# Fish_and_Microchips_Schematic.net
KiCad netlist of a schematic drawn in Altium Designer
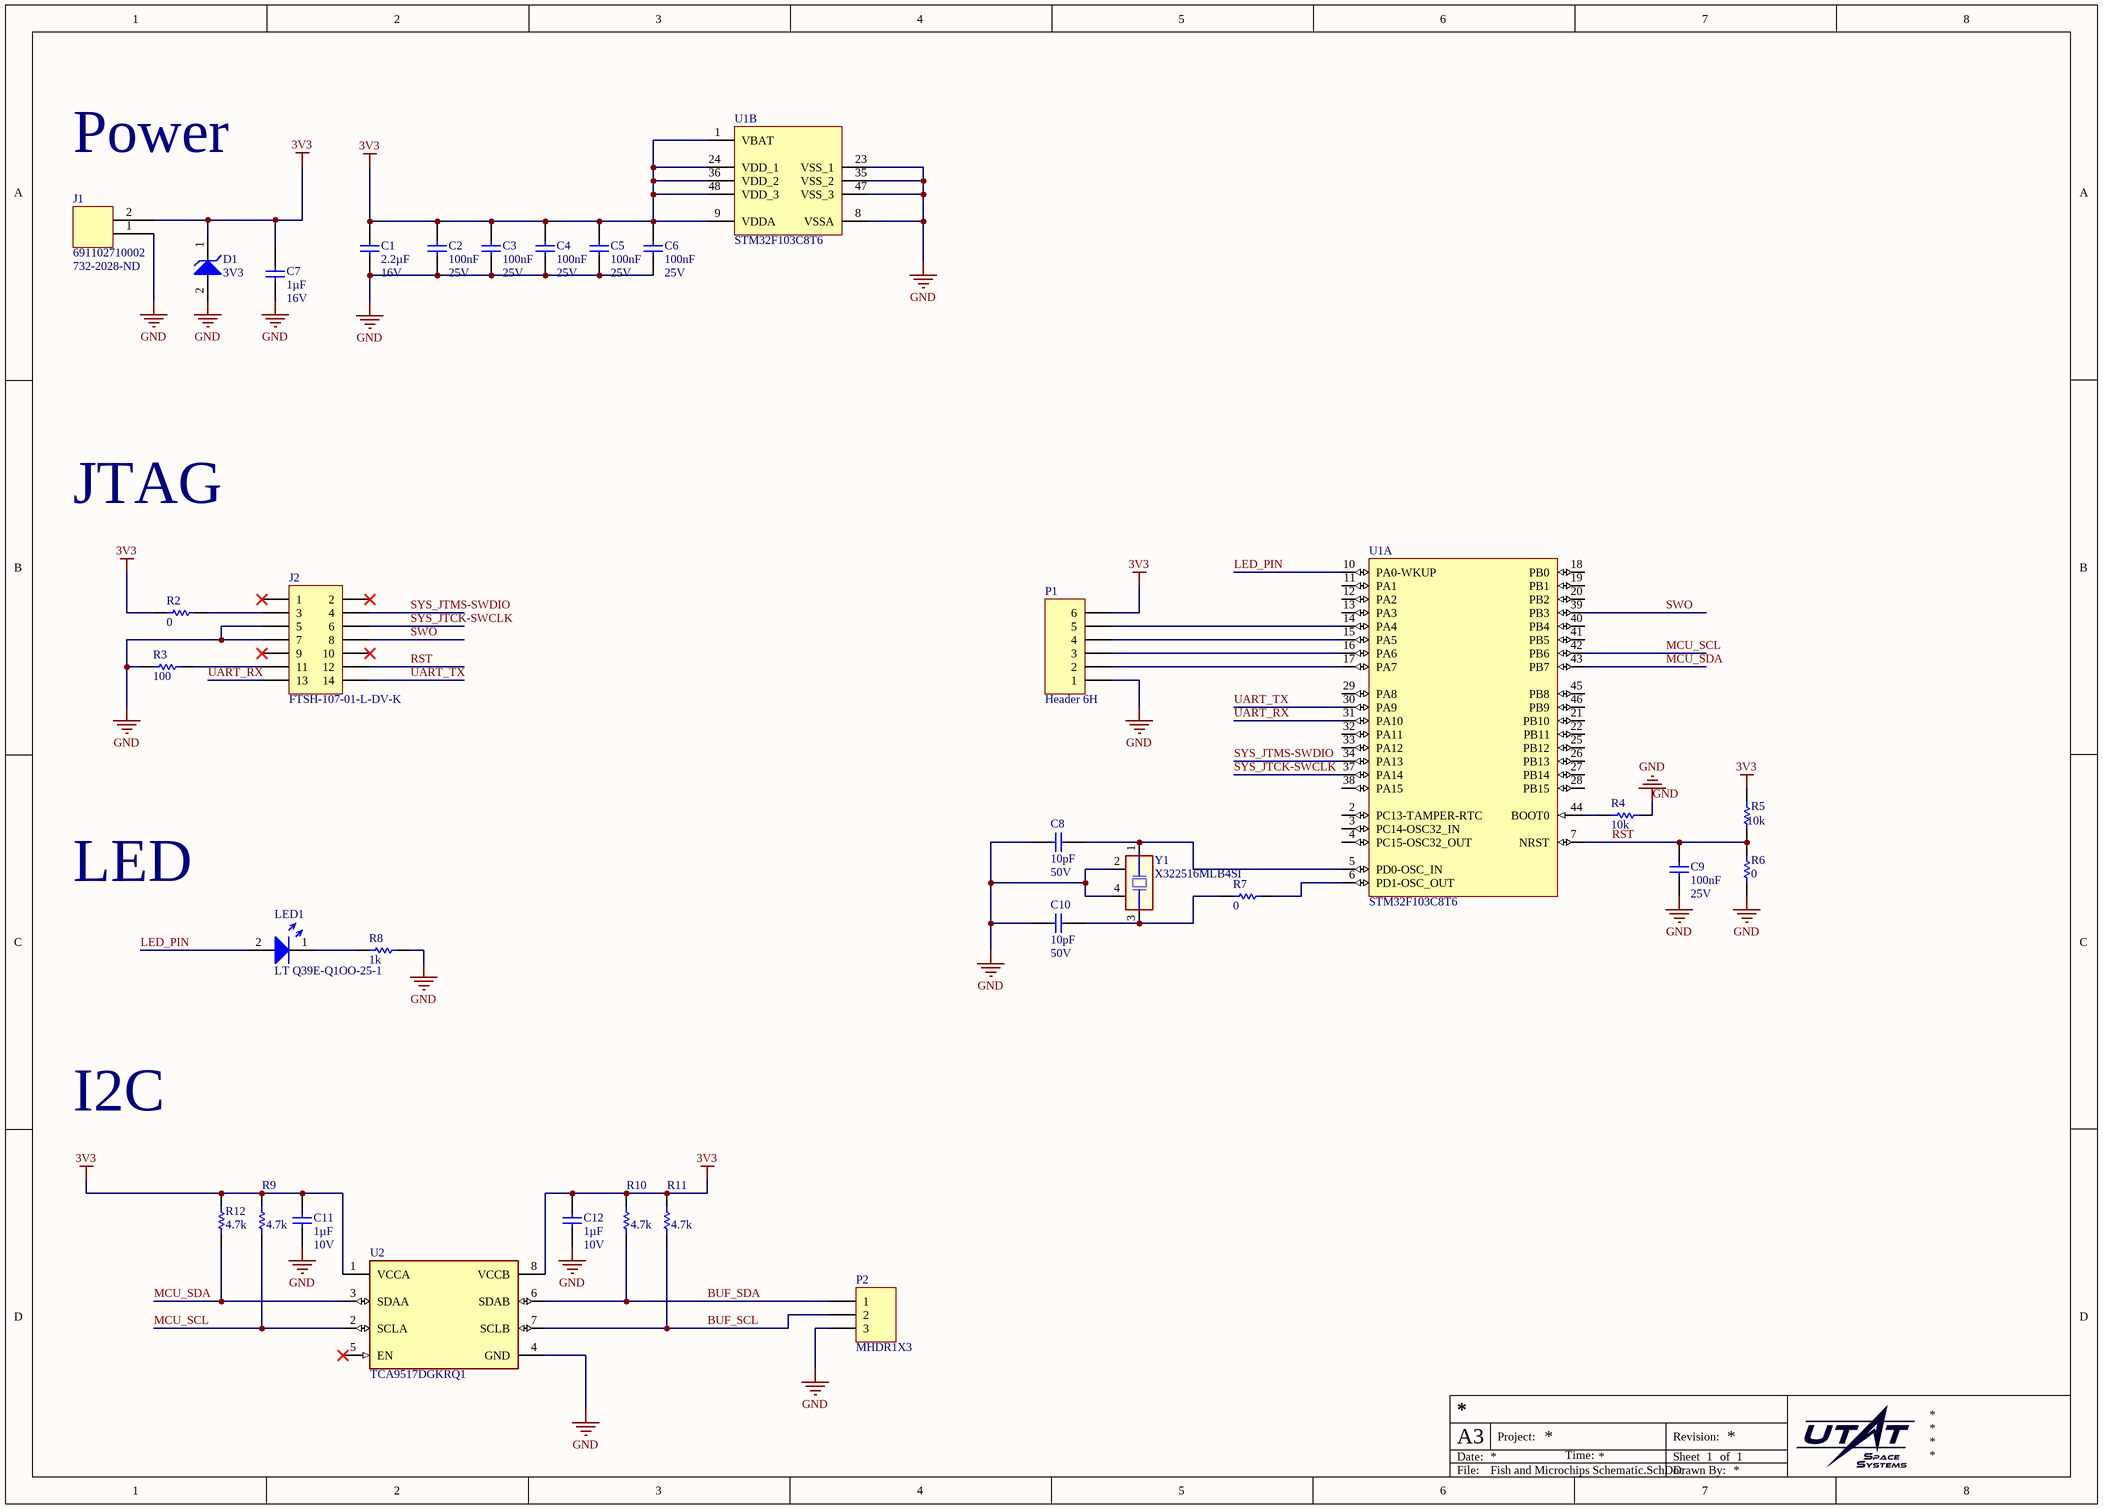
[diagram p0: Fish and Microchips Schematic.SchDoc]

(export (version "E")
  (design (tool "Eeschema 10.0.6"))
  (components
    (comp (ref "C1")
      (value "2.2µF")
      (footprint "CAP0805R")
      (description "CAP CER 2.2UF 16V X7R 0805")
      (fields
        (field (name "VOLTAGE RATING") "16V")
        (field (name "TOLERANCE") "10%")
        (field (name "MANUFACTURER") "Murata Electronics")
      )
      (libsource (lib "University of Toronto Aerospace Team") (part "Cap-2"))
    )
    (comp (ref "C2")
      (value "100nF")
      (footprint "CAP0603R")
      (description "CAP CER 0.1UF 25V X7R 0603")
      (fields
        (field (name "VOLTAGE RATING") "25V")
        (field (name "TOLERANCE") "10%")
        (field (name "MANUFACTURER") "TDK Corporation")
      )
      (libsource (lib "University of Toronto Aerospace Team") (part "Cap-2"))
    )
    (comp (ref "C3")
      (value "100nF")
      (footprint "CAP0603R")
      (description "CAP CER 0.1UF 25V X7R 0603")
      (fields
        (field (name "VOLTAGE RATING") "25V")
        (field (name "TOLERANCE") "10%")
        (field (name "MANUFACTURER") "TDK Corporation")
      )
      (libsource (lib "University of Toronto Aerospace Team") (part "Cap-2"))
    )
    (comp (ref "C4")
      (value "100nF")
      (footprint "CAP0603R")
      (description "CAP CER 0.1UF 25V X7R 0603")
      (fields
        (field (name "VOLTAGE RATING") "25V")
        (field (name "TOLERANCE") "10%")
        (field (name "MANUFACTURER") "TDK Corporation")
      )
      (libsource (lib "University of Toronto Aerospace Team") (part "Cap-2"))
    )
    (comp (ref "C5")
      (value "100nF")
      (footprint "CAP0603R")
      (description "CAP CER 0.1UF 25V X7R 0603")
      (fields
        (field (name "VOLTAGE RATING") "25V")
        (field (name "TOLERANCE") "10%")
        (field (name "MANUFACTURER") "TDK Corporation")
      )
      (libsource (lib "University of Toronto Aerospace Team") (part "Cap-2"))
    )
    (comp (ref "C6")
      (value "100nF")
      (footprint "CAP0603R")
      (description "CAP CER 0.1UF 25V X7R 0603")
      (fields
        (field (name "VOLTAGE RATING") "25V")
        (field (name "TOLERANCE") "10%")
        (field (name "MANUFACTURER") "TDK Corporation")
      )
      (libsource (lib "University of Toronto Aerospace Team") (part "Cap-2"))
    )
    (comp (ref "C7")
      (value "1µF")
      (footprint "CAP0805R")
      (description "CAP CER 1UF 16V X7R 0805")
      (fields
        (field (name "VOLTAGE RATING") "16V")
        (field (name "MANUFACTURER") "Murata Electronics")
        (field (name "TOLERANCE") "10%")
      )
      (libsource (lib "University of Toronto Aerospace Team") (part "Cap-2"))
    )
    (comp (ref "C8")
      (value "10pF")
      (footprint "CAP0402R")
      (description "CAP CER 10PF 50V C0G/NP0 0402")
      (fields
        (field (name "VOLTAGE RATING") "50V")
        (field (name "TOLERANCE") "5%")
        (field (name "MANUFACTURER") "Murata Electronics")
      )
      (libsource (lib "University of Toronto Aerospace Team") (part "Cap-2"))
    )
    (comp (ref "C9")
      (value "100nF")
      (footprint "CAP0603R")
      (description "CAP CER 0.1UF 25V X7R 0603")
      (fields
        (field (name "VOLTAGE RATING") "25V")
        (field (name "TOLERANCE") "10%")
        (field (name "MANUFACTURER") "TDK Corporation")
      )
      (libsource (lib "University of Toronto Aerospace Team") (part "Cap-2"))
    )
    (comp (ref "C10")
      (value "10pF")
      (footprint "CAP0402R")
      (description "CAP CER 10PF 50V C0G/NP0 0402")
      (fields
        (field (name "VOLTAGE RATING") "50V")
        (field (name "TOLERANCE") "5%")
        (field (name "MANUFACTURER") "Murata Electronics")
      )
      (libsource (lib "University of Toronto Aerospace Team") (part "Cap-2"))
    )
    (comp (ref "C11")
      (value "1µF")
      (footprint "CAP0805R")
      (description "CAP CER 1UF 10V X7R 0805")
      (fields
        (field (name "VOLTAGE RATING") "10V")
        (field (name "MANUFACTURER") "Taiyo Yuden")
        (field (name "TOLERANCE") "10%")
      )
      (libsource (lib "University of Toronto Aerospace Team") (part "Cap-2"))
    )
    (comp (ref "C12")
      (value "1µF")
      (footprint "CAP0805R")
      (description "CAP CER 1UF 10V X7R 0805")
      (fields
        (field (name "VOLTAGE RATING") "10V")
        (field (name "MANUFACTURER") "Taiyo Yuden")
        (field (name "TOLERANCE") "10%")
      )
      (libsource (lib "University of Toronto Aerospace Team") (part "Cap-2"))
    )
    (comp (ref "D1")
      (value "3V3")
      (footprint "ONSC-SOD-323-2-477-02_V")
      (description "Zener Diode, 3.3V V(Z), 6%, 0.3W, Silicon, Unidirectional")
      (libsource (lib "University of Toronto Aerospace Team") (part "ONSC-K1A2-2"))
    )
    (comp (ref "J1")
      (value "691102710002")
      (footprint "CON2_SCREW_5.00MM_691102710002")
      (description "2 Position Wire to Board Terminal Block Horizontal with Board 0.197\" (5.00mm) Through Hole")
      (fields
        (field (name "SUPPLIER PART NUMBER 1") "732-2028-ND")
        (field (name "MANUFACTURER") "Würth Elektronik")
      )
      (libsource (lib "University of Toronto Aerospace Team") (part "691102710002"))
    )
    (comp (ref "J2")
      (value "FTSH-107-01-L-DV-K")
      (footprint "FP-FTSH-107-01-L-DV-K-MFG")
      (description "Conn Unshrouded Header HDR 14 POS 1.27mm Solder ST Top Entry SMD TIGER CLAW™ Tube")
      (libsource (lib "University of Toronto Aerospace Team") (part "Header 7X2H"))
    )
    (comp (ref "LED1")
      (value "LT Q39E-Q1OO-25-1")
      (footprint "LED0603")
      (description "LED GREEN DIFFUSED 0603 SMD")
      (fields (field (name "MANUFACTURER") "OSRAM Opto Semiconductors Inc."))
      (libsource (lib "University of Toronto Aerospace Team") (part "LED-2"))
    )
    (comp (ref "P1")
      (value "Header 6H")
      (footprint "HDR1X6H")
      (description "Header, 6-Pin, Right Angle")
      (fields (field (name "PUBLISHER") "Altium Limited"))
      (libsource (lib "University of Toronto Aerospace Team") (part "Header 6H"))
    )
    (comp (ref "P2")
      (value "MHDR1X3")
      (footprint "MHDR1X3")
      (description "Header, 3-Pin")
      (fields (field (name "PUBLISHER") "Altium Limited"))
      (libsource (lib "University of Toronto Aerospace Team") (part "Header 3H"))
    )
    (comp (ref "R2")
      (value "0")
      (footprint "RES0805R")
      (description "RES SMD 0 OHM JUMPER 1/8W 0805")
      (fields (field (name "MANUFACTURER") "Panasonic") (field (name "POWER") "125mW"))
      (libsource (lib "University of Toronto Aerospace Team") (part "Res-2"))
    )
    (comp (ref "R3")
      (value "100")
      (footprint "RES0603R")
      (description "RES SMD 100 OHM 5% 1/10W 0603")
      (fields (field (name "POWER") "100mW") (field (name "TOLERANCE") "5%"))
      (libsource (lib "University of Toronto Aerospace Team") (part "Res-2"))
    )
    (comp (ref "R4")
      (value "10k")
      (footprint "RES0603R")
      (description "RES SMD 10K OHM 5% 1/10W 0603")
      (fields (field (name "POWER") "100mW") (field (name "TOLERANCE") "5%"))
      (libsource (lib "University of Toronto Aerospace Team") (part "Res-2"))
    )
    (comp (ref "R5")
      (value "10k")
      (footprint "RES0603R")
      (description "RES SMD 10K OHM 5% 1/10W 0603")
      (fields (field (name "POWER") "100mW") (field (name "TOLERANCE") "5%"))
      (libsource (lib "University of Toronto Aerospace Team") (part "Res-2"))
    )
    (comp (ref "R6")
      (value "0")
      (footprint "RES0805R")
      (description "RES SMD 0 OHM JUMPER 1/8W 0805")
      (fields (field (name "MANUFACTURER") "Panasonic") (field (name "POWER") "125mW"))
      (libsource (lib "University of Toronto Aerospace Team") (part "Res-2"))
    )
    (comp (ref "R7")
      (value "0")
      (footprint "RES0805R")
      (description "RES SMD 0 OHM JUMPER 1/8W 0805")
      (fields (field (name "MANUFACTURER") "Panasonic") (field (name "POWER") "125mW"))
      (libsource (lib "University of Toronto Aerospace Team") (part "Res-2"))
    )
    (comp (ref "R8")
      (value "1k")
      (footprint "RES0805R")
      (description "RES SMD 1K OHM 1% 1/8W 0805")
      (fields (field (name "MANUFACTURER") "Vishay Dale") (field (name "POWER") "125mW"))
      (libsource (lib "University of Toronto Aerospace Team") (part "Res-2"))
    )
    (comp (ref "R9")
      (value "4.7k")
      (footprint "RES0402R")
      (description "RES SMD 4.7K OHM 5% 1/10W 0402")
      (fields (field (name "TOLERANCE") "5%") (field (name "POWER") "100mW"))
      (libsource (lib "University of Toronto Aerospace Team") (part "Res-2"))
    )
    (comp (ref "R10")
      (value "4.7k")
      (footprint "RES0402R")
      (description "RES SMD 4.7K OHM 5% 1/10W 0402")
      (fields (field (name "TOLERANCE") "5%") (field (name "POWER") "100mW"))
      (libsource (lib "University of Toronto Aerospace Team") (part "Res-2"))
    )
    (comp (ref "R11")
      (value "4.7k")
      (footprint "RES0402R")
      (description "RES SMD 4.7K OHM 5% 1/10W 0402")
      (fields (field (name "TOLERANCE") "5%") (field (name "POWER") "100mW"))
      (libsource (lib "University of Toronto Aerospace Team") (part "Res-2"))
    )
    (comp (ref "R12")
      (value "4.7k")
      (footprint "RES0402R")
      (description "RES SMD 4.7K OHM 5% 1/10W 0402")
      (fields (field (name "TOLERANCE") "5%") (field (name "POWER") "100mW"))
      (libsource (lib "University of Toronto Aerospace Team") (part "Res-2"))
    )
    (comp (ref "U1")
      (value "STM32F103C8T6")
      (footprint "STM-LQFP48_M")
      (description "RISC Microcontroller, 32-Bit, FLASH, STM32 CPU, 72MHz, CMOS, PQFP48")
      (libsource (lib "University of Toronto Aerospace Team") (part "MC-ARM-STM32F103X8_B-SQ48"))
    )
    (comp (ref "U2")
      (value "TCA9517DGKRQ1")
      (footprint "FP-DGK0008A-MFG")
      (description "Voltage Level Translator Bidirectional 1 Circuit 2 Channel 8-VSSOP")
      (libsource (lib "University of Toronto Aerospace Team") (part "TCA9517DGKRQ1"))
    )
    (comp (ref "Y1")
      (value "X322516MLB4SI")
      (footprint "X322516MLB4SI-Footprint-1")
      (description "16MHz Surface Mount Crystal 9pF ±10ppm ±20ppm SMD3225-4P Crystals ROHS")
      (libsource (lib "University of Toronto Aerospace Team") (part "CRYSTAL-2"))
    )
  )
  (nets
    (net (code "1") (name "/BUF_SCL") (class "Default")
      (node (ref "P2") (pin "2") (pinfunction "2_2") (pintype "passive"))
      (node (ref "R11") (pin "1") (pinfunction "1_1") (pintype "passive"))
      (node (ref "U2") (pin "7") (pinfunction "SCLB_7") (pintype "bidirectional"))
    )
    (net (code "2") (name "/BUF_SDA") (class "Default")
      (node (ref "P2") (pin "1") (pinfunction "1_1") (pintype "passive"))
      (node (ref "R10") (pin "1") (pinfunction "1_1") (pintype "passive"))
      (node (ref "U2") (pin "6") (pinfunction "SDAB_6") (pintype "bidirectional"))
    )
    (net (code "3") (name "/LED_PIN") (class "Default")
      (node (ref "LED1") (pin "2") (pinfunction "Anode_2") (pintype "passive"))
      (node (ref "U1") (pin "10") (pinfunction "PA0-WKUP_10") (pintype "bidirectional"))
    )
    (net (code "4") (name "/MCU_SCL") (class "Default")
      (node (ref "R9") (pin "1") (pinfunction "1_1") (pintype "passive"))
      (node (ref "U1") (pin "42") (pinfunction "PB6_42") (pintype "bidirectional"))
      (node (ref "U2") (pin "2") (pinfunction "SCLA_2") (pintype "bidirectional"))
    )
    (net (code "5") (name "/MCU_SDA") (class "Default")
      (node (ref "R12") (pin "1") (pinfunction "1_1") (pintype "passive"))
      (node (ref "U1") (pin "43") (pinfunction "PB7_43") (pintype "bidirectional"))
      (node (ref "U2") (pin "3") (pinfunction "SDAA_3") (pintype "bidirectional"))
    )
    (net (code "6") (name "/RST") (class "Default")
      (node (ref "C9") (pin "2") (pinfunction "2_2") (pintype "passive"))
      (node (ref "J2") (pin "12") (pinfunction "12_12") (pintype "passive"))
      (node (ref "R5") (pin "1") (pinfunction "1_1") (pintype "passive"))
      (node (ref "R6") (pin "2") (pinfunction "2_2") (pintype "passive"))
      (node (ref "U1") (pin "7") (pinfunction "NRST_7") (pintype "bidirectional"))
    )
    (net (code "7") (name "/SWO") (class "Default")
      (node (ref "J2") (pin "8") (pinfunction "8_8") (pintype "passive"))
      (node (ref "U1") (pin "39") (pinfunction "PB3_39") (pintype "bidirectional"))
    )
    (net (code "8") (name "/SYS_JTCK-SWCLK") (class "Default")
      (node (ref "J2") (pin "6") (pinfunction "6_6") (pintype "passive"))
      (node (ref "U1") (pin "37") (pinfunction "PA14_37") (pintype "bidirectional"))
    )
    (net (code "9") (name "/SYS_JTMS-SWDIO") (class "Default")
      (node (ref "J2") (pin "4") (pinfunction "4_4") (pintype "passive"))
      (node (ref "U1") (pin "34") (pinfunction "PA13_34") (pintype "bidirectional"))
    )
    (net (code "10") (name "/UART_RX") (class "Default")
      (node (ref "J2") (pin "13") (pinfunction "13_13") (pintype "passive"))
      (node (ref "U1") (pin "31") (pinfunction "PA10_31") (pintype "bidirectional"))
    )
    (net (code "11") (name "/UART_TX") (class "Default")
      (node (ref "J2") (pin "14") (pinfunction "14_14") (pintype "passive"))
      (node (ref "U1") (pin "30") (pinfunction "PA9_30") (pintype "bidirectional"))
    )
    (net (code "12") (name "3V3") (class "Default")
      (node (ref "C1") (pin "2") (pinfunction "2_2") (pintype "passive"))
      (node (ref "C11") (pin "2") (pinfunction "2_2") (pintype "passive"))
      (node (ref "C12") (pin "2") (pinfunction "2_2") (pintype "passive"))
      (node (ref "C2") (pin "2") (pinfunction "2_2") (pintype "passive"))
      (node (ref "C3") (pin "2") (pinfunction "2_2") (pintype "passive"))
      (node (ref "C4") (pin "2") (pinfunction "2_2") (pintype "passive"))
      (node (ref "C5") (pin "2") (pinfunction "2_2") (pintype "passive"))
      (node (ref "C6") (pin "2") (pinfunction "2_2") (pintype "passive"))
      (node (ref "C7") (pin "2") (pinfunction "2_2") (pintype "passive"))
      (node (ref "D1") (pin "1") (pinfunction "K_1") (pintype "passive"))
      (node (ref "J1") (pin "2") (pinfunction "2_2") (pintype "passive"))
      (node (ref "P1") (pin "6") (pinfunction "6_6") (pintype "passive"))
      (node (ref "R10") (pin "2") (pinfunction "2_2") (pintype "passive"))
      (node (ref "R11") (pin "2") (pinfunction "2_2") (pintype "passive"))
      (node (ref "R12") (pin "2") (pinfunction "2_2") (pintype "passive"))
      (node (ref "R2") (pin "1") (pinfunction "1_1") (pintype "passive"))
      (node (ref "R5") (pin "2") (pinfunction "2_2") (pintype "passive"))
      (node (ref "R9") (pin "2") (pinfunction "2_2") (pintype "passive"))
      (node (ref "U1") (pin "1") (pinfunction "VBAT_1") (pintype "power_in"))
      (node (ref "U1") (pin "24") (pinfunction "VDD_1_24") (pintype "power_in"))
      (node (ref "U1") (pin "36") (pinfunction "VDD_2_36") (pintype "power_in"))
      (node (ref "U1") (pin "48") (pinfunction "VDD_3_48") (pintype "power_in"))
      (node (ref "U1") (pin "9") (pinfunction "VDDA_9") (pintype "power_in"))
      (node (ref "U2") (pin "1") (pinfunction "VCCA_1") (pintype "power_in"))
      (node (ref "U2") (pin "8") (pinfunction "VCCB_8") (pintype "power_in"))
    )
    (net (code "13") (name "GND") (class "Default")
      (node (ref "C1") (pin "1") (pinfunction "1_1") (pintype "passive"))
      (node (ref "C10") (pin "1") (pinfunction "1_1") (pintype "passive"))
      (node (ref "C11") (pin "1") (pinfunction "1_1") (pintype "passive"))
      (node (ref "C12") (pin "1") (pinfunction "1_1") (pintype "passive"))
      (node (ref "C2") (pin "1") (pinfunction "1_1") (pintype "passive"))
      (node (ref "C3") (pin "1") (pinfunction "1_1") (pintype "passive"))
      (node (ref "C4") (pin "1") (pinfunction "1_1") (pintype "passive"))
      (node (ref "C5") (pin "1") (pinfunction "1_1") (pintype "passive"))
      (node (ref "C6") (pin "1") (pinfunction "1_1") (pintype "passive"))
      (node (ref "C7") (pin "1") (pinfunction "1_1") (pintype "passive"))
      (node (ref "C8") (pin "2") (pinfunction "2_2") (pintype "passive"))
      (node (ref "C9") (pin "1") (pinfunction "1_1") (pintype "passive"))
      (node (ref "D1") (pin "2") (pinfunction "A_2") (pintype "passive"))
      (node (ref "J1") (pin "1") (pinfunction "1_1") (pintype "passive"))
      (node (ref "J2") (pin "5") (pinfunction "5_5") (pintype "passive"))
      (node (ref "J2") (pin "7") (pinfunction "7_7") (pintype "passive"))
      (node (ref "P1") (pin "1") (pinfunction "1_1") (pintype "passive"))
      (node (ref "P2") (pin "3") (pinfunction "3_3") (pintype "passive"))
      (node (ref "R3") (pin "1") (pinfunction "1_1") (pintype "passive"))
      (node (ref "R4") (pin "2") (pinfunction "2_2") (pintype "passive"))
      (node (ref "R6") (pin "1") (pinfunction "1_1") (pintype "passive"))
      (node (ref "R8") (pin "2") (pinfunction "2_2") (pintype "passive"))
      (node (ref "U1") (pin "23") (pinfunction "VSS_1_23") (pintype "power_in"))
      (node (ref "U1") (pin "35") (pinfunction "VSS_2_35") (pintype "power_in"))
      (node (ref "U1") (pin "47") (pinfunction "VSS_3_47") (pintype "power_in"))
      (node (ref "U1") (pin "8") (pinfunction "VSSA_8") (pintype "power_in"))
      (node (ref "U2") (pin "4") (pinfunction "GND_4") (pintype "power_in"))
      (node (ref "Y1") (pin "2") (pinfunction "GND_2") (pintype "passive"))
      (node (ref "Y1") (pin "4") (pinfunction "GND_4") (pintype "passive"))
    )
    (net (code "14") (name "Net-(J2-Pad3)") (class "Default")
      (node (ref "J2") (pin "3") (pinfunction "3_3") (pintype "passive"))
      (node (ref "R2") (pin "2") (pinfunction "2_2") (pintype "passive"))
    )
    (net (code "15") (name "Net-(J2-Pad11)") (class "Default")
      (node (ref "J2") (pin "11") (pinfunction "11_11") (pintype "passive"))
      (node (ref "R3") (pin "2") (pinfunction "2_2") (pintype "passive"))
    )
    (net (code "16") (name "Net-(LED1-Cathode)") (class "Default")
      (node (ref "LED1") (pin "1") (pinfunction "Cathode_1") (pintype "passive"))
      (node (ref "R8") (pin "1") (pinfunction "1_1") (pintype "passive"))
    )
    (net (code "17") (name "Net-(U1A-BOOT0)") (class "Default")
      (node (ref "R4") (pin "1") (pinfunction "1_1") (pintype "passive"))
      (node (ref "U1") (pin "44") (pinfunction "BOOT0_44") (pintype "input"))
    )
    (net (code "18") (name "Net-(U1A-PA4)") (class "Default")
      (node (ref "P1") (pin "5") (pinfunction "5_5") (pintype "passive"))
      (node (ref "U1") (pin "14") (pinfunction "PA4_14") (pintype "bidirectional"))
    )
    (net (code "19") (name "Net-(U1A-PA5)") (class "Default")
      (node (ref "P1") (pin "4") (pinfunction "4_4") (pintype "passive"))
      (node (ref "U1") (pin "15") (pinfunction "PA5_15") (pintype "bidirectional"))
    )
    (net (code "20") (name "Net-(U1A-PA6)") (class "Default")
      (node (ref "P1") (pin "3") (pinfunction "3_3") (pintype "passive"))
      (node (ref "U1") (pin "16") (pinfunction "PA6_16") (pintype "bidirectional"))
    )
    (net (code "21") (name "Net-(U1A-PA7)") (class "Default")
      (node (ref "P1") (pin "2") (pinfunction "2_2") (pintype "passive"))
      (node (ref "U1") (pin "17") (pinfunction "PA7_17") (pintype "bidirectional"))
    )
    (net (code "22") (name "Net-(U1A-PD0-OSC_IN)") (class "Default")
      (node (ref "C8") (pin "1") (pinfunction "1_1") (pintype "passive"))
      (node (ref "U1") (pin "5") (pinfunction "PD0-OSC_IN_5") (pintype "bidirectional"))
      (node (ref "Y1") (pin "1") (pinfunction "OSC1_1") (pintype "passive"))
    )
    (net (code "23") (name "Net-(U1A-PD1-OSC_OUT)") (class "Default")
      (node (ref "R7") (pin "2") (pinfunction "2_2") (pintype "passive"))
      (node (ref "U1") (pin "6") (pinfunction "PD1-OSC_OUT_6") (pintype "bidirectional"))
    )
    (net (code "24") (name "Net-(Y1-OSC2)") (class "Default")
      (node (ref "C10") (pin "2") (pinfunction "2_2") (pintype "passive"))
      (node (ref "R7") (pin "1") (pinfunction "1_1") (pintype "passive"))
      (node (ref "Y1") (pin "3") (pinfunction "OSC2_3") (pintype "passive"))
    )
    (net (code "25") (name "unconnected-(J2-Pad1)") (class "Default")
      (node (ref "J2") (pin "1") (pinfunction "1_1") (pintype "passive+no_connect"))
    )
    (net (code "26") (name "unconnected-(J2-Pad2)") (class "Default")
      (node (ref "J2") (pin "2") (pinfunction "2_2") (pintype "passive+no_connect"))
    )
    (net (code "27") (name "unconnected-(J2-Pad9)") (class "Default")
      (node (ref "J2") (pin "9") (pinfunction "9_9") (pintype "passive+no_connect"))
    )
    (net (code "28") (name "unconnected-(J2-Pad10)") (class "Default")
      (node (ref "J2") (pin "10") (pinfunction "10_10") (pintype "passive+no_connect"))
    )
    (net (code "29") (name "unconnected-(U1A-PA1-Pad11)") (class "Default")
      (node (ref "U1") (pin "11") (pinfunction "PA1_11") (pintype "bidirectional"))
    )
    (net (code "30") (name "unconnected-(U1A-PA2-Pad12)") (class "Default")
      (node (ref "U1") (pin "12") (pinfunction "PA2_12") (pintype "bidirectional"))
    )
    (net (code "31") (name "unconnected-(U1A-PA3-Pad13)") (class "Default")
      (node (ref "U1") (pin "13") (pinfunction "PA3_13") (pintype "bidirectional"))
    )
    (net (code "32") (name "unconnected-(U1A-PA8-Pad29)") (class "Default")
      (node (ref "U1") (pin "29") (pinfunction "PA8_29") (pintype "bidirectional"))
    )
    (net (code "33") (name "unconnected-(U1A-PA11-Pad32)") (class "Default")
      (node (ref "U1") (pin "32") (pinfunction "PA11_32") (pintype "bidirectional"))
    )
    (net (code "34") (name "unconnected-(U1A-PA12-Pad33)") (class "Default")
      (node (ref "U1") (pin "33") (pinfunction "PA12_33") (pintype "bidirectional"))
    )
    (net (code "35") (name "unconnected-(U1A-PA15-Pad38)") (class "Default")
      (node (ref "U1") (pin "38") (pinfunction "PA15_38") (pintype "bidirectional"))
    )
    (net (code "36") (name "unconnected-(U1A-PB0-Pad18)") (class "Default")
      (node (ref "U1") (pin "18") (pinfunction "PB0_18") (pintype "bidirectional"))
    )
    (net (code "37") (name "unconnected-(U1A-PB1-Pad19)") (class "Default")
      (node (ref "U1") (pin "19") (pinfunction "PB1_19") (pintype "bidirectional"))
    )
    (net (code "38") (name "unconnected-(U1A-PB2-Pad20)") (class "Default")
      (node (ref "U1") (pin "20") (pinfunction "PB2_20") (pintype "bidirectional"))
    )
    (net (code "39") (name "unconnected-(U1A-PB4-Pad40)") (class "Default")
      (node (ref "U1") (pin "40") (pinfunction "PB4_40") (pintype "bidirectional"))
    )
    (net (code "40") (name "unconnected-(U1A-PB5-Pad41)") (class "Default")
      (node (ref "U1") (pin "41") (pinfunction "PB5_41") (pintype "bidirectional"))
    )
    (net (code "41") (name "unconnected-(U1A-PB8-Pad45)") (class "Default")
      (node (ref "U1") (pin "45") (pinfunction "PB8_45") (pintype "bidirectional"))
    )
    (net (code "42") (name "unconnected-(U1A-PB9-Pad46)") (class "Default")
      (node (ref "U1") (pin "46") (pinfunction "PB9_46") (pintype "bidirectional"))
    )
    (net (code "43") (name "unconnected-(U1A-PB10-Pad21)") (class "Default")
      (node (ref "U1") (pin "21") (pinfunction "PB10_21") (pintype "bidirectional"))
    )
    (net (code "44") (name "unconnected-(U1A-PB11-Pad22)") (class "Default")
      (node (ref "U1") (pin "22") (pinfunction "PB11_22") (pintype "bidirectional"))
    )
    (net (code "45") (name "unconnected-(U1A-PB12-Pad25)") (class "Default")
      (node (ref "U1") (pin "25") (pinfunction "PB12_25") (pintype "bidirectional"))
    )
    (net (code "46") (name "unconnected-(U1A-PB13-Pad26)") (class "Default")
      (node (ref "U1") (pin "26") (pinfunction "PB13_26") (pintype "bidirectional"))
    )
    (net (code "47") (name "unconnected-(U1A-PB14-Pad27)") (class "Default")
      (node (ref "U1") (pin "27") (pinfunction "PB14_27") (pintype "bidirectional"))
    )
    (net (code "48") (name "unconnected-(U1A-PB15-Pad28)") (class "Default")
      (node (ref "U1") (pin "28") (pinfunction "PB15_28") (pintype "bidirectional"))
    )
    (net (code "49") (name "unconnected-(U1A-PC13-TAMPER-RTC-Pad2)") (class "Default")
      (node (ref "U1") (pin "2") (pinfunction "PC13-TAMPER-RTC_2") (pintype "bidirectional"))
    )
    (net (code "50") (name "unconnected-(U1A-PC14-OSC32_IN-Pad3)") (class "Default")
      (node (ref "U1") (pin "3") (pinfunction "PC14-OSC32_IN_3") (pintype "bidirectional"))
    )
    (net (code "51") (name "unconnected-(U1A-PC15-OSC32_OUT-Pad4)") (class "Default")
      (node (ref "U1") (pin "4") (pinfunction "PC15-OSC32_OUT_4") (pintype "bidirectional"))
    )
    (net (code "52") (name "unconnected-(U2-EN-Pad5)") (class "Default")
      (node (ref "U2") (pin "5") (pinfunction "EN_5") (pintype "input+no_connect"))
    )
  )
)
